# V_11.net
KiCad netlist of a schematic drawn in Altium Designer
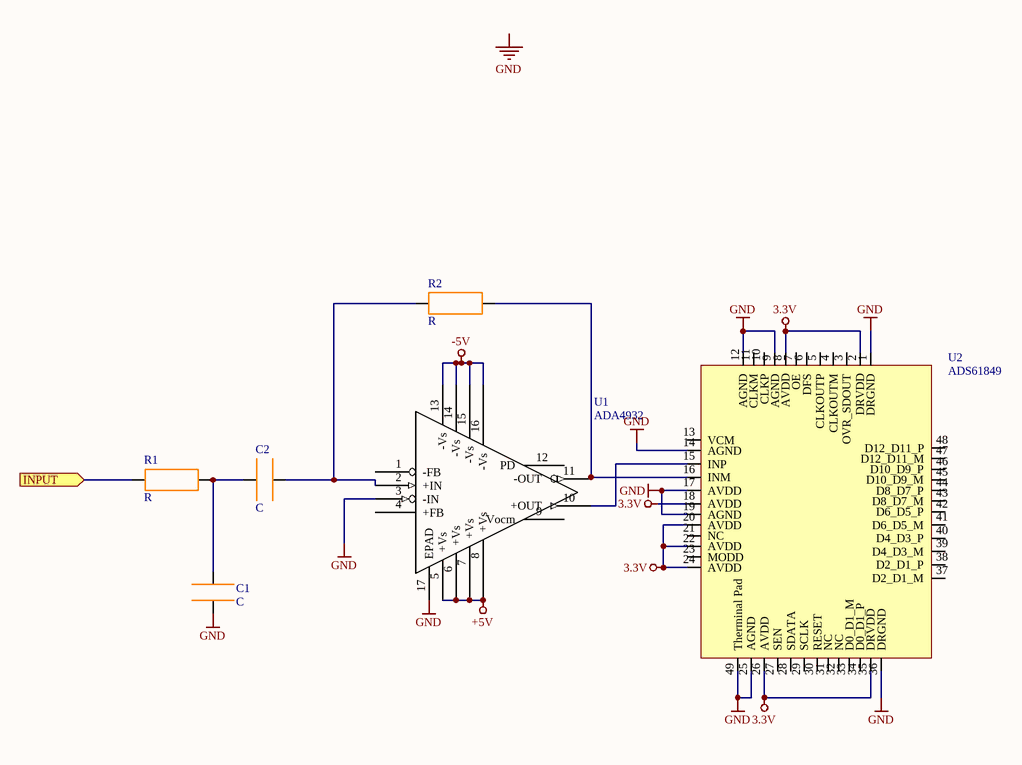
[diagram p0: V_11.SchDoc]

(export (version "E")
  (design (tool "Eeschema 10.0.6"))
  (components
    (comp (ref "C1") (value "C") (footprint "C_0805") (libsource (lib "V_11") (part "C")))
    (comp (ref "C2") (value "C") (footprint "C_0805") (libsource (lib "V_11") (part "C")))
    (comp (ref "R1") (value "R") (footprint "R_0805") (libsource (lib "V_11") (part "R")))
    (comp (ref "R2") (value "R") (footprint "R_0805") (libsource (lib "V_11") (part "R")))
    (comp (ref "U1") (value "ADA4932") (footprint "V_11:ADA4932") (libsource (lib "V_11") (part "ADA4932")))
    (comp (ref "U2")
      (value "ADS61849")
      (footprint "V_11:ADS61B49")
      (libsource (lib "V_11") (part "ADS61849"))
    )
  )
  (nets
    (net (code "1") (name "+5V") (class "Default")
      (node (ref "U1") (pin "5") (pinfunction "+Vs_5") (pintype "power_in"))
      (node (ref "U1") (pin "6") (pinfunction "+Vs_6") (pintype "power_in"))
      (node (ref "U1") (pin "7") (pinfunction "+Vs_7") (pintype "power_in"))
      (node (ref "U1") (pin "8") (pinfunction "+Vs_8") (pintype "power_in"))
    )
    (net (code "2") (name "-5V") (class "Default")
      (node (ref "U1") (pin "13") (pinfunction "-Vs_13") (pintype "power_in"))
      (node (ref "U1") (pin "14") (pinfunction "-Vs_14") (pintype "power_in"))
      (node (ref "U1") (pin "15") (pinfunction "-Vs_15") (pintype "power_in"))
      (node (ref "U1") (pin "16") (pinfunction "-Vs_16") (pintype "power_in"))
    )
    (net (code "3") (name "/INPUT") (class "Default")
      (node (ref "R1") (pin "1") (pinfunction "1_1") (pintype "passive"))
    )
    (net (code "4") (name "3.3V") (class "Default")
      (node (ref "U2") (pin "18") (pinfunction "AVDD_18") (pintype "passive"))
      (node (ref "U2") (pin "2") (pinfunction "DRVDD_2") (pintype "passive"))
      (node (ref "U2") (pin "20") (pinfunction "AVDD_20") (pintype "passive"))
      (node (ref "U2") (pin "22") (pinfunction "AVDD_22") (pintype "passive"))
      (node (ref "U2") (pin "24") (pinfunction "AVDD_24") (pintype "passive"))
      (node (ref "U2") (pin "26") (pinfunction "AVDD_26") (pintype "passive"))
      (node (ref "U2") (pin "35") (pinfunction "DRVDD_35") (pintype "passive"))
      (node (ref "U2") (pin "8") (pinfunction "AVDD_8") (pintype "passive"))
    )
    (net (code "5") (name "GND") (class "Default")
      (node (ref "C1") (pin "5") (pinfunction "5_5") (pintype "passive"))
      (node (ref "U1") (pin "17") (pinfunction "EPAD_17") (pintype "power_in"))
      (node (ref "U1") (pin "3") (pinfunction "-IN_3") (pintype "input"))
      (node (ref "U2") (pin "1") (pinfunction "DRGND_1") (pintype "passive"))
      (node (ref "U2") (pin "12") (pinfunction "AGND_12") (pintype "passive"))
      (node (ref "U2") (pin "14") (pinfunction "AGND_14") (pintype "passive"))
      (node (ref "U2") (pin "17") (pinfunction "AVDD_17") (pintype "passive"))
      (node (ref "U2") (pin "19") (pinfunction "AGND_19") (pintype "passive"))
      (node (ref "U2") (pin "25") (pinfunction "AGND_25") (pintype "passive"))
      (node (ref "U2") (pin "36") (pinfunction "DRGND_36") (pintype "passive"))
      (node (ref "U2") (pin "49") (pinfunction "Therminal_Pad_49") (pintype "passive"))
      (node (ref "U2") (pin "9") (pinfunction "AGND_9") (pintype "passive"))
    )
    (net (code "6") (name "Net-(C1-Pad4)") (class "Default")
      (node (ref "C1") (pin "4") (pinfunction "4_4") (pintype "passive"))
      (node (ref "C2") (pin "4") (pinfunction "4_4") (pintype "passive"))
      (node (ref "R1") (pin "2") (pinfunction "2_2") (pintype "passive"))
    )
    (net (code "7") (name "Net-(U1-+IN)") (class "Default")
      (node (ref "C2") (pin "5") (pinfunction "5_5") (pintype "passive"))
      (node (ref "R2") (pin "1") (pinfunction "1_1") (pintype "passive"))
      (node (ref "U1") (pin "2") (pinfunction "+IN_2") (pintype "input"))
    )
    (net (code "8") (name "Net-(U1-+OUT)") (class "Default")
      (node (ref "U1") (pin "10") (pinfunction "+OUT_10") (pintype "output"))
      (node (ref "U2") (pin "15") (pinfunction "INP_15") (pintype "passive"))
    )
    (net (code "9") (name "Net-(U1--OUT)") (class "Default")
      (node (ref "R2") (pin "2") (pinfunction "2_2") (pintype "passive"))
      (node (ref "U1") (pin "11") (pinfunction "-OUT_11") (pintype "output"))
      (node (ref "U2") (pin "16") (pinfunction "INM_16") (pintype "passive"))
    )
    (net (code "10") (name "unconnected-(U1-+FB-Pad4)") (class "Default")
      (node (ref "U1") (pin "4") (pinfunction "+FB_4") (pintype "passive"))
    )
    (net (code "11") (name "unconnected-(U1--FB-Pad1)") (class "Default")
      (node (ref "U1") (pin "1") (pinfunction "-FB_1") (pintype "passive"))
    )
    (net (code "12") (name "unconnected-(U1-PD-Pad12)") (class "Default")
      (node (ref "U1") (pin "12") (pinfunction "PD_12") (pintype "passive"))
    )
    (net (code "13") (name "unconnected-(U1-Vocm-Pad9)") (class "Default")
      (node (ref "U1") (pin "9") (pinfunction "Vocm_9") (pintype "power_in"))
    )
    (net (code "14") (name "unconnected-(U2-CLKM-Pad11)") (class "Default")
      (node (ref "U2") (pin "11") (pinfunction "CLKM_11") (pintype "passive"))
    )
    (net (code "15") (name "unconnected-(U2-CLKOUTM-Pad4)") (class "Default")
      (node (ref "U2") (pin "4") (pinfunction "CLKOUTM_4") (pintype "passive"))
    )
    (net (code "16") (name "unconnected-(U2-CLKOUTP-Pad5)") (class "Default")
      (node (ref "U2") (pin "5") (pinfunction "CLKOUTP_5") (pintype "passive"))
    )
    (net (code "17") (name "unconnected-(U2-CLKP-Pad10)") (class "Default")
      (node (ref "U2") (pin "10") (pinfunction "CLKP_10") (pintype "passive"))
    )
    (net (code "18") (name "unconnected-(U2-D0_D1_M-Pad33)") (class "Default")
      (node (ref "U2") (pin "33") (pinfunction "D0_D1_M_33") (pintype "passive"))
    )
    (net (code "19") (name "unconnected-(U2-D0_D1_P-Pad34)") (class "Default")
      (node (ref "U2") (pin "34") (pinfunction "D0_D1_P_34") (pintype "passive"))
    )
    (net (code "20") (name "unconnected-(U2-D2_D1_M-Pad37)") (class "Default")
      (node (ref "U2") (pin "37") (pinfunction "D2_D1_M_37") (pintype "passive"))
    )
    (net (code "21") (name "unconnected-(U2-D2_D1_P-Pad38)") (class "Default")
      (node (ref "U2") (pin "38") (pinfunction "D2_D1_P_38") (pintype "passive"))
    )
    (net (code "22") (name "unconnected-(U2-D4_D3_M-Pad39)") (class "Default")
      (node (ref "U2") (pin "39") (pinfunction "D4_D3_M_39") (pintype "passive"))
    )
    (net (code "23") (name "unconnected-(U2-D4_D3_P-Pad40)") (class "Default")
      (node (ref "U2") (pin "40") (pinfunction "D4_D3_P_40") (pintype "passive"))
    )
    (net (code "24") (name "unconnected-(U2-D6_D5_M-Pad41)") (class "Default")
      (node (ref "U2") (pin "41") (pinfunction "D6_D5_M_41") (pintype "passive"))
    )
    (net (code "25") (name "unconnected-(U2-D6_D5_P-Pad42)") (class "Default")
      (node (ref "U2") (pin "42") (pinfunction "D6_D5_P_42") (pintype "passive"))
    )
    (net (code "26") (name "unconnected-(U2-D8_D7_M-Pad43)") (class "Default")
      (node (ref "U2") (pin "43") (pinfunction "D8_D7_M_43") (pintype "passive"))
    )
    (net (code "27") (name "unconnected-(U2-D8_D7_P-Pad44)") (class "Default")
      (node (ref "U2") (pin "44") (pinfunction "D8_D7_P_44") (pintype "passive"))
    )
    (net (code "28") (name "unconnected-(U2-D10_D9_M-Pad45)") (class "Default")
      (node (ref "U2") (pin "45") (pinfunction "D10_D9_M_45") (pintype "passive"))
    )
    (net (code "29") (name "unconnected-(U2-D10_D9_P-Pad46)") (class "Default")
      (node (ref "U2") (pin "46") (pinfunction "D10_D9_P_46") (pintype "passive"))
    )
    (net (code "30") (name "unconnected-(U2-D12_D11_M-Pad47)") (class "Default")
      (node (ref "U2") (pin "47") (pinfunction "D12_D11_M_47") (pintype "passive"))
    )
    (net (code "31") (name "unconnected-(U2-D12_D11_P-Pad48)") (class "Default")
      (node (ref "U2") (pin "48") (pinfunction "D12_D11_P_48") (pintype "passive"))
    )
    (net (code "32") (name "unconnected-(U2-DFS-Pad6)") (class "Default")
      (node (ref "U2") (pin "6") (pinfunction "DFS_6") (pintype "passive"))
    )
    (net (code "33") (name "unconnected-(U2-MODD-Pad23)") (class "Default")
      (node (ref "U2") (pin "23") (pinfunction "MODD_23") (pintype "passive"))
    )
    (net (code "34") (name "unconnected-(U2-NC-Pad21)") (class "Default")
      (node (ref "U2") (pin "21") (pinfunction "NC_21") (pintype "passive"))
    )
    (net (code "35") (name "unconnected-(U2-NC-Pad31)") (class "Default")
      (node (ref "U2") (pin "31") (pinfunction "NC_31") (pintype "passive"))
    )
    (net (code "36") (name "unconnected-(U2-NC-Pad32)") (class "Default")
      (node (ref "U2") (pin "32") (pinfunction "NC_32") (pintype "passive"))
    )
    (net (code "37") (name "unconnected-(U2-OE-Pad7)") (class "Default")
      (node (ref "U2") (pin "7") (pinfunction "OE_7") (pintype "passive"))
    )
    (net (code "38") (name "unconnected-(U2-OVR_SDOUT-Pad3)") (class "Default")
      (node (ref "U2") (pin "3") (pinfunction "OVR_SDOUT_3") (pintype "passive"))
    )
    (net (code "39") (name "unconnected-(U2-RESET-Pad30)") (class "Default")
      (node (ref "U2") (pin "30") (pinfunction "RESET_30") (pintype "passive"))
    )
    (net (code "40") (name "unconnected-(U2-SCLK-Pad29)") (class "Default")
      (node (ref "U2") (pin "29") (pinfunction "SCLK_29") (pintype "passive"))
    )
    (net (code "41") (name "unconnected-(U2-SDATA-Pad28)") (class "Default")
      (node (ref "U2") (pin "28") (pinfunction "SDATA_28") (pintype "passive"))
    )
    (net (code "42") (name "unconnected-(U2-SEN-Pad27)") (class "Default")
      (node (ref "U2") (pin "27") (pinfunction "SEN_27") (pintype "passive"))
    )
    (net (code "43") (name "unconnected-(U2-VCM-Pad13)") (class "Default")
      (node (ref "U2") (pin "13") (pinfunction "VCM_13") (pintype "passive"))
    )
  )
)
